# MT3608_200mA.net
KiCad netlist of a schematic drawn in Altium Designer
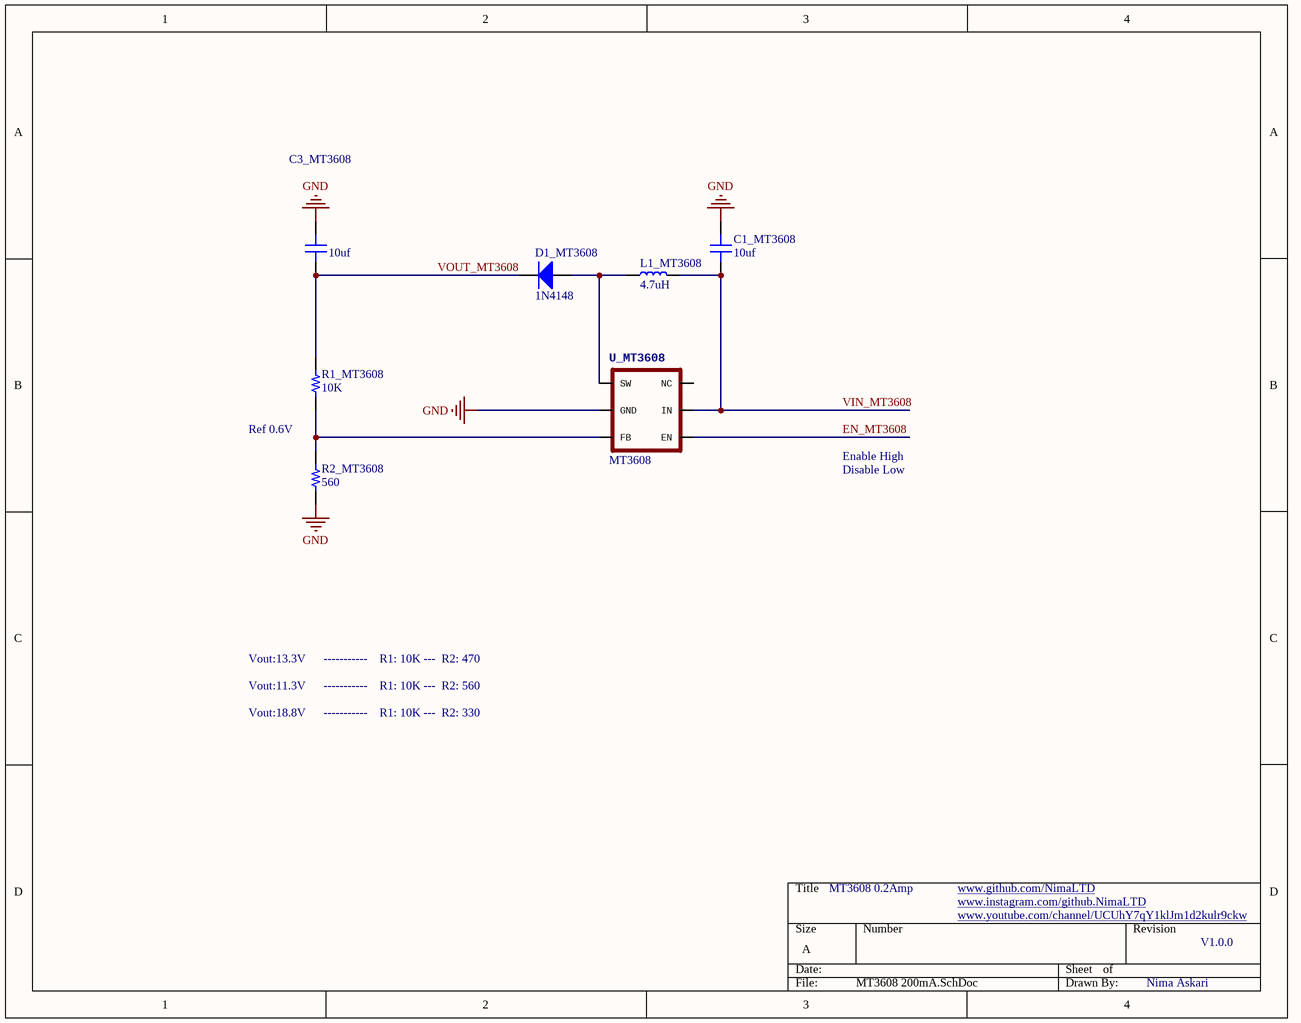
[diagram p0: MT3608 200mA.SchDoc]

(export (version "E")
  (design (tool "Eeschema 10.0.6"))
  (components
    (comp (ref "C1_MT3608")
      (value "10uf")
      (footprint "CAP 1206")
      (description "SMT Capacitor")
      (libsource (lib "CAPACITOR") (part "Cap SMD 1206"))
    )
    (comp (ref "C3_MT3608")
      (value "10uf")
      (footprint "CAP 1206")
      (description "SMT Capacitor")
      (libsource (lib "CAPACITOR") (part "Cap SMD 1206"))
    )
    (comp (ref "D1_MT3608")
      (value "1N4148 SMD")
      (footprint "SOD80")
      (description "Signal Diode")
      (fields (field (name "PARAMETER 1") "1N4148"))
      (libsource (lib "DIODE") (part "1N4148 SMD"))
    )
    (comp (ref "L1_MT3608")
      (value "4.7uH")
      (footprint "IND 3X3")
      (description "SMT Inductor")
      (fields (field (name "Comment") "Inductor SMD POWER 3X3mm"))
      (libsource (lib "INDUCTOR") (part "Inductor SMD POWER 3X3mm"))
    )
    (comp (ref "R1_MT3608")
      (value "10K")
      (footprint "RES 0805")
      (description "SMD Resistor")
      (libsource (lib "RESISTOR") (part "Res SMD 0805"))
    )
    (comp (ref "R2_MT3608")
      (value "560")
      (footprint "RES 0805")
      (description "SMD Resistor")
      (libsource (lib "RESISTOR") (part "Res SMD 0805"))
    )
    (comp (ref "U_MT3608")
      (value "MT3608")
      (footprint "SOT23-6")
      (description "Boost")
      (fields (field (name "PARAMETER") "MT3608"))
      (libsource (lib "IC") (part "MT3608"))
    )
  )
  (nets
    (net (code "1") (name "/EN_MT3608") (class "Default")
      (node (ref "U_MT3608") (pin "4") (pinfunction "EN_4") (pintype "passive"))
    )
    (net (code "2") (name "/VIN_MT3608") (class "Default")
      (node (ref "C1_MT3608") (pin "1") (pinfunction "1_1") (pintype "passive"))
      (node (ref "L1_MT3608") (pin "2") (pinfunction "2_2") (pintype "passive"))
      (node (ref "U_MT3608") (pin "5") (pinfunction "IN_5") (pintype "passive"))
    )
    (net (code "3") (name "/VOUT_MT3608") (class "Default")
      (node (ref "C3_MT3608") (pin "1") (pinfunction "1_1") (pintype "passive"))
      (node (ref "D1_MT3608") (pin "2") (pinfunction "K_2") (pintype "passive"))
      (node (ref "R1_MT3608") (pin "2") (pinfunction "2_2") (pintype "passive"))
    )
    (net (code "4") (name "GND") (class "Default")
      (node (ref "C1_MT3608") (pin "2") (pinfunction "2_2") (pintype "passive"))
      (node (ref "C3_MT3608") (pin "2") (pinfunction "2_2") (pintype "passive"))
      (node (ref "R2_MT3608") (pin "1") (pinfunction "1_1") (pintype "passive"))
      (node (ref "U_MT3608") (pin "2") (pinfunction "GND_2") (pintype "passive"))
    )
    (net (code "5") (name "Net-(D1_MT3608-A)") (class "Default")
      (node (ref "D1_MT3608") (pin "1") (pinfunction "A_1") (pintype "passive"))
      (node (ref "L1_MT3608") (pin "1") (pinfunction "1_1") (pintype "passive"))
      (node (ref "U_MT3608") (pin "1") (pinfunction "SW_1") (pintype "passive"))
    )
    (net (code "6") (name "Net-(U_MT3608-FB)") (class "Default")
      (node (ref "R1_MT3608") (pin "1") (pinfunction "1_1") (pintype "passive"))
      (node (ref "R2_MT3608") (pin "2") (pinfunction "2_2") (pintype "passive"))
      (node (ref "U_MT3608") (pin "3") (pinfunction "FB_3") (pintype "passive"))
    )
    (net (code "7") (name "unconnected-(U_MT3608-NC-Pad6)") (class "Default")
      (node (ref "U_MT3608") (pin "6") (pinfunction "NC_6") (pintype "passive"))
    )
  )
)
